# STIM300IMU.net
KiCad netlist of a schematic drawn in Altium Designer
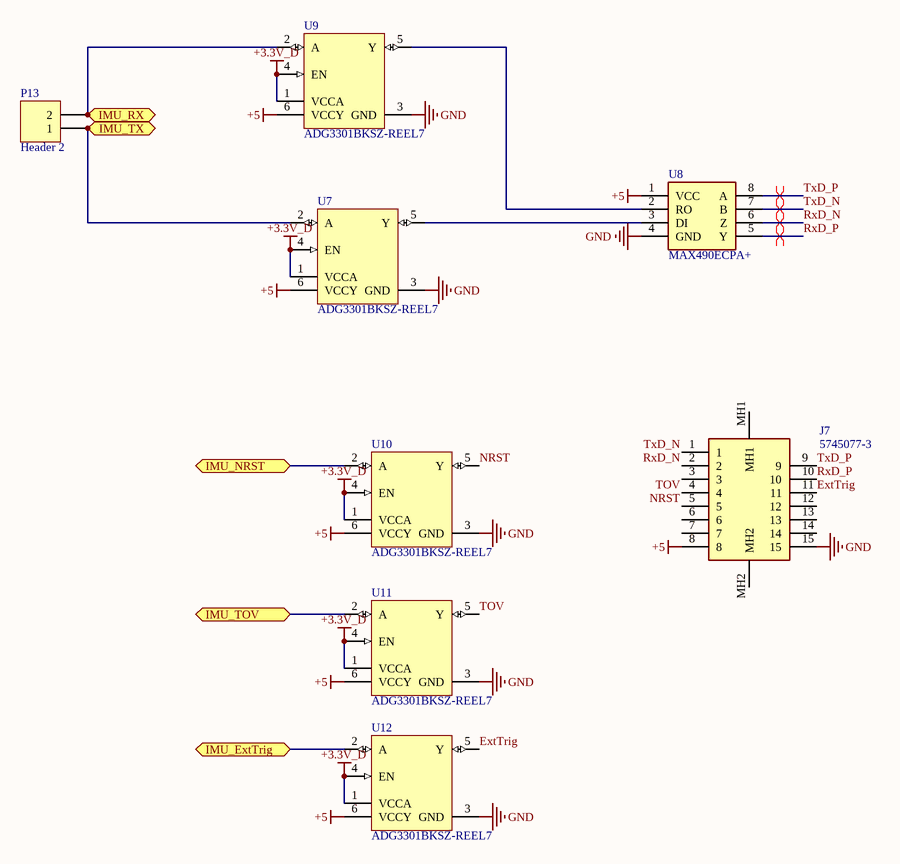
[diagram p0: STIM300IMU.SchDoc]

(export (version "E")
  (design (tool "Eeschema 10.0.6"))
  (components
    (comp (ref "J7")
      (value "5745077-3")
      (footprint "2301840-1")
      (description "Connector")
      (libsource (lib "*") (part "5745077-3"))
    )
    (comp (ref "P13")
      (value "Header 2")
      (footprint "HDR1X2")
      (description "Header, 2-Pin")
      (fields (field (name "PUBLISHER") "Altium Limited"))
      (libsource (lib "Miscellaneous Connectors") (part "Header 2"))
    )
    (comp (ref "U7")
      (value "ADG3301BKSZ-REEL7")
      (footprint "ADI-KS-6_N")
      (fields (field (name "MANUFACTURER") "Analog Devices"))
      (libsource (lib "Altium Content Vault") (part "ADI-ADG3301-KS-6"))
    )
    (comp (ref "U8")
      (value "MAX490ECPA+")
      (footprint "SamacSys:DIP762W56P254L938H457Q8N")
      (description "Integrated Circuit")
      (fields (field (name "MOUSER PART NUMBER") "700-MAX490ECPA"))
      (libsource (lib "SamacSys") (part "MAX490ECPA+"))
    )
    (comp (ref "U9")
      (value "ADG3301BKSZ-REEL7")
      (footprint "ADI-KS-6_N")
      (fields (field (name "MANUFACTURER") "Analog Devices"))
      (libsource (lib "Altium Content Vault") (part "ADI-ADG3301-KS-6"))
    )
    (comp (ref "U10")
      (value "ADG3301BKSZ-REEL7")
      (footprint "ADI-KS-6_N")
      (fields (field (name "MANUFACTURER") "Analog Devices"))
      (libsource (lib "Altium Content Vault") (part "ADI-ADG3301-KS-6"))
    )
    (comp (ref "U11")
      (value "ADG3301BKSZ-REEL7")
      (footprint "ADI-KS-6_N")
      (fields (field (name "MANUFACTURER") "Analog Devices"))
      (libsource (lib "Altium Content Vault") (part "ADI-ADG3301-KS-6"))
    )
    (comp (ref "U12")
      (value "ADG3301BKSZ-REEL7")
      (footprint "ADI-KS-6_N")
      (fields (field (name "MANUFACTURER") "Analog Devices"))
      (libsource (lib "Altium Content Vault") (part "ADI-ADG3301-KS-6"))
    )
  )
  (nets
    (net (code "1") (name "+3.3V_D") (class "Default")
      (node (ref "U10") (pin "1") (pinfunction "VCCA_1") (pintype "power_in"))
      (node (ref "U10") (pin "4") (pinfunction "EN_4") (pintype "input"))
      (node (ref "U11") (pin "1") (pinfunction "VCCA_1") (pintype "power_in"))
      (node (ref "U11") (pin "4") (pinfunction "EN_4") (pintype "input"))
      (node (ref "U12") (pin "1") (pinfunction "VCCA_1") (pintype "power_in"))
      (node (ref "U12") (pin "4") (pinfunction "EN_4") (pintype "input"))
      (node (ref "U7") (pin "1") (pinfunction "VCCA_1") (pintype "power_in"))
      (node (ref "U7") (pin "4") (pinfunction "EN_4") (pintype "input"))
      (node (ref "U9") (pin "1") (pinfunction "VCCA_1") (pintype "power_in"))
      (node (ref "U9") (pin "4") (pinfunction "EN_4") (pintype "input"))
    )
    (net (code "2") (name "+5") (class "Default")
      (node (ref "J7") (pin "8") (pinfunction "8_8") (pintype "passive"))
      (node (ref "U10") (pin "6") (pinfunction "VCCY_6") (pintype "power_in"))
      (node (ref "U11") (pin "6") (pinfunction "VCCY_6") (pintype "power_in"))
      (node (ref "U12") (pin "6") (pinfunction "VCCY_6") (pintype "power_in"))
      (node (ref "U7") (pin "6") (pinfunction "VCCY_6") (pintype "power_in"))
      (node (ref "U8") (pin "1") (pinfunction "VCC_1") (pintype "passive"))
      (node (ref "U9") (pin "6") (pinfunction "VCCY_6") (pintype "power_in"))
    )
    (net (code "3") (name "/ExtTrig") (class "Default")
      (node (ref "J7") (pin "11") (pinfunction "11_11") (pintype "passive"))
      (node (ref "U12") (pin "5") (pinfunction "Y_5") (pintype "bidirectional"))
    )
    (net (code "4") (name "/IMU_ExtTrig") (class "Default")
      (node (ref "U12") (pin "2") (pinfunction "A_2") (pintype "bidirectional"))
    )
    (net (code "5") (name "/IMU_NRST") (class "Default")
      (node (ref "U10") (pin "2") (pinfunction "A_2") (pintype "bidirectional"))
    )
    (net (code "6") (name "/IMU_RX") (class "Default")
      (node (ref "P13") (pin "2") (pinfunction "2_2") (pintype "passive"))
      (node (ref "U9") (pin "2") (pinfunction "A_2") (pintype "bidirectional"))
    )
    (net (code "7") (name "/IMU_TOV") (class "Default")
      (node (ref "U11") (pin "2") (pinfunction "A_2") (pintype "bidirectional"))
    )
    (net (code "8") (name "/IMU_TX") (class "Default")
      (node (ref "P13") (pin "1") (pinfunction "1_1") (pintype "passive"))
      (node (ref "U7") (pin "2") (pinfunction "A_2") (pintype "bidirectional"))
    )
    (net (code "9") (name "/NRST") (class "Default")
      (node (ref "J7") (pin "5") (pinfunction "5_5") (pintype "passive"))
      (node (ref "U10") (pin "5") (pinfunction "Y_5") (pintype "bidirectional"))
    )
    (net (code "10") (name "/RxD_N") (class "Default")
      (node (ref "J7") (pin "2") (pinfunction "2_2") (pintype "passive"))
      (node (ref "U8") (pin "6") (pinfunction "Z_6") (pintype "passive"))
    )
    (net (code "11") (name "/RxD_P") (class "Default")
      (node (ref "J7") (pin "10") (pinfunction "10_10") (pintype "passive"))
      (node (ref "U8") (pin "5") (pinfunction "Y_5") (pintype "passive"))
    )
    (net (code "12") (name "/TOV") (class "Default")
      (node (ref "J7") (pin "4") (pinfunction "4_4") (pintype "passive"))
      (node (ref "U11") (pin "5") (pinfunction "Y_5") (pintype "bidirectional"))
    )
    (net (code "13") (name "/TxD_N") (class "Default")
      (node (ref "J7") (pin "1") (pinfunction "1_1") (pintype "passive"))
      (node (ref "U8") (pin "7") (pinfunction "B_7") (pintype "passive"))
    )
    (net (code "14") (name "/TxD_P") (class "Default")
      (node (ref "J7") (pin "9") (pinfunction "9_9") (pintype "passive"))
      (node (ref "U8") (pin "8") (pinfunction "A_8") (pintype "passive"))
    )
    (net (code "15") (name "GND") (class "Default")
      (node (ref "J7") (pin "15") (pinfunction "15_15") (pintype "passive"))
      (node (ref "U10") (pin "3") (pinfunction "GND_3") (pintype "power_in"))
      (node (ref "U11") (pin "3") (pinfunction "GND_3") (pintype "power_in"))
      (node (ref "U12") (pin "3") (pinfunction "GND_3") (pintype "power_in"))
      (node (ref "U7") (pin "3") (pinfunction "GND_3") (pintype "power_in"))
      (node (ref "U8") (pin "4") (pinfunction "GND_4") (pintype "passive"))
      (node (ref "U9") (pin "3") (pinfunction "GND_3") (pintype "power_in"))
    )
    (net (code "16") (name "Net-(U7-Y)") (class "Default")
      (node (ref "U7") (pin "5") (pinfunction "Y_5") (pintype "bidirectional"))
      (node (ref "U8") (pin "3") (pinfunction "DI_3") (pintype "passive"))
    )
    (net (code "17") (name "Net-(U8-RO)") (class "Default")
      (node (ref "U8") (pin "2") (pinfunction "RO_2") (pintype "passive"))
      (node (ref "U9") (pin "5") (pinfunction "Y_5") (pintype "bidirectional"))
    )
    (net (code "18") (name "unconnected-(J7-Pad3)") (class "Default")
      (node (ref "J7") (pin "3") (pinfunction "3_3") (pintype "passive"))
    )
    (net (code "19") (name "unconnected-(J7-Pad6)") (class "Default")
      (node (ref "J7") (pin "6") (pinfunction "6_6") (pintype "passive"))
    )
    (net (code "20") (name "unconnected-(J7-Pad7)") (class "Default")
      (node (ref "J7") (pin "7") (pinfunction "7_7") (pintype "passive"))
    )
    (net (code "21") (name "unconnected-(J7-Pad12)") (class "Default")
      (node (ref "J7") (pin "12") (pinfunction "12_12") (pintype "passive"))
    )
    (net (code "22") (name "unconnected-(J7-Pad13)") (class "Default")
      (node (ref "J7") (pin "13") (pinfunction "13_13") (pintype "passive"))
    )
    (net (code "23") (name "unconnected-(J7-Pad14)") (class "Default")
      (node (ref "J7") (pin "14") (pinfunction "14_14") (pintype "passive"))
    )
    (net (code "24") (name "unconnected-(J7-PadMH1)") (class "Default")
      (node (ref "J7") (pin "MH1") (pinfunction "MH1_MH1") (pintype "passive"))
    )
    (net (code "25") (name "unconnected-(J7-PadMH2)") (class "Default")
      (node (ref "J7") (pin "MH2") (pinfunction "MH2_MH2") (pintype "passive"))
    )
  )
)
